# Receptor.net
KiCad netlist of a schematic drawn in Altium Designer
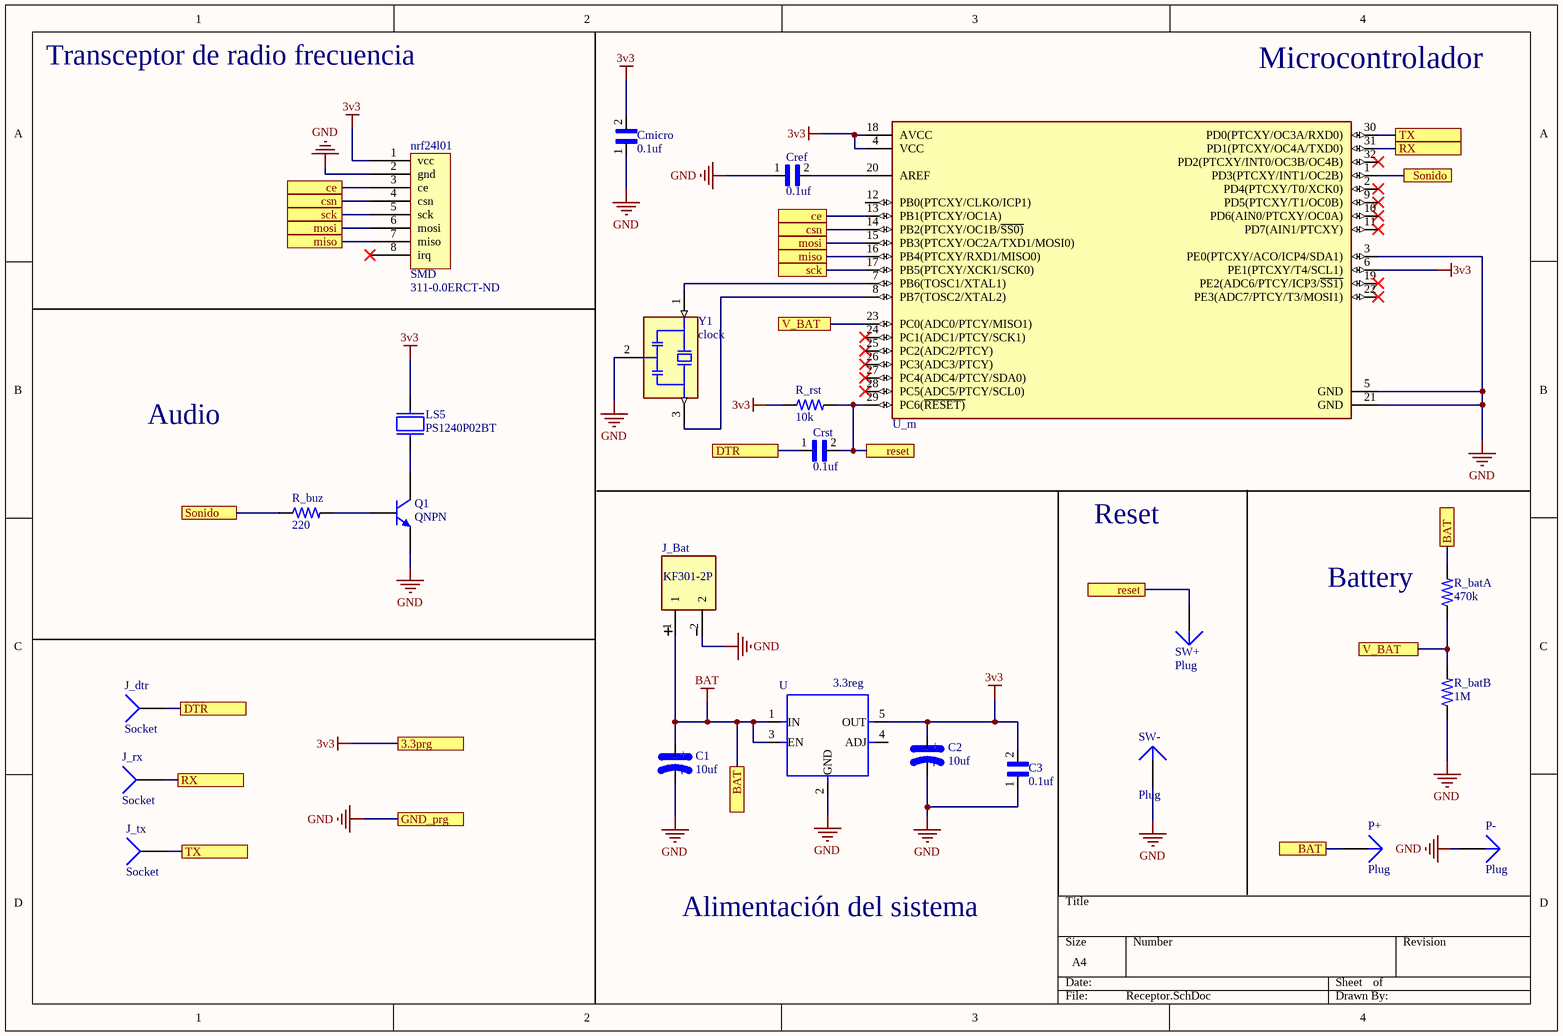
[diagram p0: Receptor.SchDoc]

(export (version "E")
  (design (tool "Eeschema 10.0.6"))
  (components
    (comp (ref "C1")
      (value "10uf")
      (footprint "CT1206")
      (description "10ÂµF Molded Tantalum Capacitors 20V 1206 _3216 Metric_ 5Ohm")
      (fields (field (name "MF") "KEMET") (field (name "MP") "T491A106M020AT"))
      (libsource (lib "1206_tantalio") (part "TANTALUM-SMD-10UF-20V-20%(1206)"))
    )
    (comp (ref "C2")
      (value "10uf")
      (footprint "CT1206")
      (description "10ÂµF Molded Tantalum Capacitors 20V 1206 _3216 Metric_ 5Ohm")
      (fields (field (name "MF") "KEMET") (field (name "MP") "T491A106M020AT"))
      (libsource (lib "1206_tantalio") (part "TANTALUM-SMD-10UF-20V-20%(1206)"))
    )
    (comp (ref "C3")
      (value "0.1uf")
      (footprint "CAPC2012X94N")
      (description "10000pF Â±5% 16V Ceramic Capacitor X7R 0805 _2012 Metric_")
      (fields (field (name "MF") "AVX") (field (name "MP") "0805YC103J4T2A"))
      (libsource (lib "") (part "0805YC103J4T2A_1"))
    )
    (comp (ref "Cmicro")
      (value "0.1uf")
      (footprint "CAPC2012X94N")
      (description "10000pF Â±5% 16V Ceramic Capacitor X7R 0805 _2012 Metric_")
      (fields (field (name "MF") "AVX") (field (name "MP") "0805YC103J4T2A"))
      (libsource (lib "") (part "0805YC103J4T2A_1"))
    )
    (comp (ref "Cref")
      (value "0.1uf")
      (footprint "CAPC2012X94N")
      (description "10000pF Â±5% 16V Ceramic Capacitor X7R 0805 _2012 Metric_")
      (fields (field (name "MF") "AVX") (field (name "MP") "0805YC103J4T2A"))
      (libsource (lib "v2CAP0805") (part "0805YC103J4T2A"))
    )
    (comp (ref "Crst")
      (value "0.1uf")
      (footprint "CAPC2012X94N")
      (description "10000pF Â±5% 16V Ceramic Capacitor X7R 0805 _2012 Metric_")
      (fields (field (name "MF") "AVX") (field (name "MP") "0805YC103J4T2A"))
      (libsource (lib "v2CAP0805") (part "0805YC103J4T2A"))
    )
    (comp (ref "J_Bat")
      (value "KF301-2P")
      (footprint "HANDSON_KF301-2P")
      (description "2 Pin Terminal Block 5mm Pitch")
      (fields (field (name "MF") "Handson Technology"))
      (libsource (lib "bornera") (part "KF301-2P"))
    )
    (comp (ref "J_dtr")
      (value "Socket")
      (footprint "PIN1")
      (fields (field (name "PUBLISHER") "Altium Limited"))
      (libsource (lib "Miscellaneous Connectors") (part "Socket"))
    )
    (comp (ref "J_rx")
      (value "Socket")
      (footprint "PIN1")
      (fields (field (name "PUBLISHER") "Altium Limited"))
      (libsource (lib "Miscellaneous Connectors") (part "Socket"))
    )
    (comp (ref "J_tx")
      (value "Socket")
      (footprint "PIN1")
      (fields (field (name "PUBLISHER") "Altium Limited"))
      (libsource (lib "Miscellaneous Connectors") (part "Socket"))
    )
    (comp (ref "LS5")
      (value "PS1240P02BT")
      (footprint "XDCR_PS1240P02BT")
      (description "Buzzers Transducer, Externally Driven Piezo 3V 4kHz 60dB @ 3V, 10cm Through Hole PC Pins")
      (fields (field (name "MF") "TDK"))
      (libsource (lib "buzzerGrande") (part "PS1240P02BT"))
    )
    (comp (ref "nrf24l01")
      (value "SMD")
      (footprint "NRF24L01")
      (fields (field (name "SUPPLIER PART NUMBER 1") "311-0.0ERCT-ND"))
      (libsource (lib "Schlib1") (part "nrf24l01_smd"))
    )
    (comp (ref "P+")
      (value "Plug")
      (footprint "PIN1")
      (fields (field (name "PUBLISHER") "Altium Limited"))
      (libsource (lib "Miscellaneous Connectors") (part "Plug"))
    )
    (comp (ref "P-")
      (value "Plug")
      (footprint "PIN1")
      (fields (field (name "PUBLISHER") "Altium Limited"))
      (libsource (lib "Miscellaneous Connectors") (part "Plug"))
    )
    (comp (ref "Q1")
      (value "QNPN")
      (footprint "SOT-23B_N")
      (description "NPN Bipolar Transistor")
      (fields (field (name "PUBLISHER") "Altium Limited"))
      (libsource (lib "Miscellaneous Devices") (part "QNPN"))
    )
    (comp (ref "R_batA")
      (value "470k")
      (footprint "RESC2012X65N")
      (description "RES 0.33 OHM 1% 1/4W 0805")
      (fields (field (name "MF") "TE Connectivity") (field (name "TOLERANCE") "1%"))
      (libsource (lib "RES0805") (part "2-2176053-0"))
    )
    (comp (ref "R_batB")
      (value "1M")
      (footprint "RESC2012X65N")
      (description "RES 0.33 OHM 1% 1/4W 0805")
      (fields (field (name "MF") "TE Connectivity") (field (name "TOLERANCE") "1%"))
      (libsource (lib "RES0805") (part "2-2176053-0"))
    )
    (comp (ref "R_buz")
      (value "220")
      (footprint "RESC2012X65N")
      (description "RES 0.33 OHM 1% 1/4W 0805")
      (fields (field (name "MF") "TE Connectivity") (field (name "TOLERANCE") "1%"))
      (libsource (lib "RES0805") (part "2-2176053-0"))
    )
    (comp (ref "R_rst")
      (value "10k")
      (footprint "RESC2012X65N")
      (description "RES 0.33 OHM 1% 1/4W 0805")
      (fields (field (name "MF") "TE Connectivity") (field (name "TOLERANCE") "1%"))
      (libsource (lib "RES0805") (part "2-2176053-0"))
    )
    (comp (ref "SW+")
      (value "Plug")
      (footprint "PIN1")
      (fields (field (name "PUBLISHER") "Altium Limited"))
      (libsource (lib "Miscellaneous Connectors") (part "Plug"))
    )
    (comp (ref "SW-")
      (value "Plug")
      (footprint "PIN1")
      (fields (field (name "PUBLISHER") "Altium Limited"))
      (libsource (lib "Miscellaneous Connectors") (part "Plug"))
    )
    (comp (ref "U")
      (value "3.3reg")
      (footprint "SOT-23-5")
      (description "Linear Voltage Regulator IC 1 Output 150mA SOT-23-5")
      (fields (field (name "MP") "MIC5205-3.3YM5-TR") (field (name "MF") "Microchip"))
      (libsource (lib "3.3mini") (part "PMIC-MIC5205-3.3YMSTR(SOT23-5)"))
    )
    (comp (ref "U_m")
      (value "ATMEGA328PB-AUR")
      (footprint "Microchip_C04-074_IPC_C")
      (libsource (lib "IC_Microchip_ATMEGA328PB-AUR_eec") (part "ATMEGA328PB-AUR"))
    )
    (comp (ref "Y1")
      (value "clock")
      (footprint "OSC_CSTCE8M00G52-R0")
      (description "8MHz Ceramic Resonator Built in Capacitor 10pF Â±0.2% -20Â°C ~ 80Â°C Surface Mount")
      (fields (field (name "MF") "Murata") (field (name "MP") "CSTCE8M00G52-R0"))
      (libsource (lib "CSTCE8M00G52-R0") (part "CSTCE8M00G52-R0"))
    )
  )
  (nets
    (net (code "1") (name "/DTR") (class "Default")
      (node (ref "Crst") (pin "1") (pinfunction "1_1") (pintype "passive"))
      (node (ref "J_dtr") (pin "1") (pinfunction "1_1") (pintype "passive"))
    )
    (net (code "2") (name "/RX") (class "Default")
      (node (ref "J_rx") (pin "1") (pinfunction "1_1") (pintype "passive"))
      (node (ref "U_m") (pin "31") (pinfunction "PD1(PTCXY/OC4A/TXD0)_31") (pintype "bidirectional"))
    )
    (net (code "3") (name "/Sonido") (class "Default")
      (node (ref "R_buz") (pin "1") (pinfunction "1_1") (pintype "passive"))
      (node (ref "U_m") (pin "1") (pinfunction "PD3(PTCXY/INT1/OC2B)_1") (pintype "bidirectional"))
    )
    (net (code "4") (name "/TX") (class "Default")
      (node (ref "J_tx") (pin "1") (pinfunction "1_1") (pintype "passive"))
      (node (ref "U_m") (pin "30") (pinfunction "PD0(PTCXY/OC3A/RXD0)_30") (pintype "bidirectional"))
    )
    (net (code "5") (name "/V_BAT") (class "Default")
      (node (ref "R_batA") (pin "1") (pinfunction "1_1") (pintype "passive"))
      (node (ref "R_batB") (pin "2") (pinfunction "2_2") (pintype "passive"))
      (node (ref "U_m") (pin "23") (pinfunction "PC0(ADC0/PTCY/MISO1)_23") (pintype "bidirectional"))
    )
    (net (code "6") (name "/ce") (class "Default")
      (node (ref "U_m") (pin "13") (pinfunction "PB1(PTCXY/OC1A)_13") (pintype "bidirectional"))
      (node (ref "nrf24l01") (pin "3") (pinfunction "ce_3") (pintype "passive"))
    )
    (net (code "7") (name "/csn") (class "Default")
      (node (ref "U_m") (pin "14") (pinfunction "PB2(PTCXY/OC1B/~{SS0)}_14") (pintype "bidirectional"))
      (node (ref "nrf24l01") (pin "4") (pinfunction "csn_4") (pintype "passive"))
    )
    (net (code "8") (name "/miso") (class "Default")
      (node (ref "U_m") (pin "16") (pinfunction "PB4(PTCXY/RXD1/MISO0)_16") (pintype "bidirectional"))
      (node (ref "nrf24l01") (pin "7") (pinfunction "miso_7") (pintype "passive"))
    )
    (net (code "9") (name "/mosi") (class "Default")
      (node (ref "U_m") (pin "15") (pinfunction "PB3(PTCXY/OC2A/TXD1/MOSI0)_15") (pintype "bidirectional"))
      (node (ref "nrf24l01") (pin "6") (pinfunction "mosi_6") (pintype "passive"))
    )
    (net (code "10") (name "/reset") (class "Default")
      (node (ref "Crst") (pin "2") (pinfunction "2_2") (pintype "passive"))
      (node (ref "R_rst") (pin "2") (pinfunction "2_2") (pintype "passive"))
      (node (ref "SW+") (pin "1") (pinfunction "1_1") (pintype "passive"))
      (node (ref "U_m") (pin "29") (pinfunction "PC6(~{RESET)}_29") (pintype "bidirectional"))
    )
    (net (code "11") (name "/sck") (class "Default")
      (node (ref "U_m") (pin "17") (pinfunction "PB5(PTCXY/XCK1/SCK0)_17") (pintype "bidirectional"))
      (node (ref "nrf24l01") (pin "5") (pinfunction "sck_5") (pintype "passive"))
    )
    (net (code "12") (name "3v3") (class "Default")
      (node (ref "C2") (pin "POS") (pinfunction "POS_POS") (pintype "passive"))
      (node (ref "C3") (pin "2") (pinfunction "2_2") (pintype "passive"))
      (node (ref "Cmicro") (pin "2") (pinfunction "2_2") (pintype "passive"))
      (node (ref "LS5") (pin "1") (pinfunction "1_1") (pintype "passive"))
      (node (ref "R_rst") (pin "1") (pinfunction "1_1") (pintype "passive"))
      (node (ref "U") (pin "5") (pinfunction "OUT_5") (pintype "bidirectional"))
      (node (ref "U_m") (pin "18") (pinfunction "AVCC_18") (pintype "power_in"))
      (node (ref "U_m") (pin "4") (pinfunction "VCC_4") (pintype "power_in"))
      (node (ref "U_m") (pin "6") (pinfunction "PE1(PTCXY/T4/SCL1)_6") (pintype "bidirectional"))
      (node (ref "nrf24l01") (pin "1") (pinfunction "vcc_1") (pintype "passive"))
    )
    (net (code "13") (name "BAT") (class "Default")
      (node (ref "C1") (pin "POS") (pinfunction "POS_POS") (pintype "passive"))
      (node (ref "J_Bat") (pin "1") (pinfunction "1_1") (pintype "passive"))
      (node (ref "P+") (pin "1") (pinfunction "1_1") (pintype "passive"))
      (node (ref "R_batA") (pin "2") (pinfunction "2_2") (pintype "passive"))
      (node (ref "U") (pin "1") (pinfunction "IN_1") (pintype "bidirectional"))
      (node (ref "U") (pin "3") (pinfunction "EN_3") (pintype "bidirectional"))
    )
    (net (code "14") (name "GND") (class "Default")
      (node (ref "C1") (pin "NEG") (pinfunction "NEG_NEG") (pintype "passive"))
      (node (ref "C2") (pin "NEG") (pinfunction "NEG_NEG") (pintype "passive"))
      (node (ref "C3") (pin "1") (pinfunction "1_1") (pintype "passive"))
      (node (ref "Cmicro") (pin "1") (pinfunction "1_1") (pintype "passive"))
      (node (ref "Cref") (pin "1") (pinfunction "1_1") (pintype "passive"))
      (node (ref "J_Bat") (pin "2") (pinfunction "2_2") (pintype "passive"))
      (node (ref "P-") (pin "1") (pinfunction "1_1") (pintype "passive"))
      (node (ref "Q1") (pin "3") (pinfunction "E_3") (pintype "passive"))
      (node (ref "R_batB") (pin "1") (pinfunction "1_1") (pintype "passive"))
      (node (ref "SW-") (pin "1") (pinfunction "1_1") (pintype "passive"))
      (node (ref "U") (pin "2") (pinfunction "GND_2") (pintype "bidirectional"))
      (node (ref "U_m") (pin "21") (pinfunction "GND_21") (pintype "power_in"))
      (node (ref "U_m") (pin "3") (pinfunction "PE0(PTCXY/ACO/ICP4/SDA1)_3") (pintype "bidirectional"))
      (node (ref "U_m") (pin "5") (pinfunction "GND_5") (pintype "power_in"))
      (node (ref "Y1") (pin "2") (pinfunction "GND_2") (pintype "power_in"))
      (node (ref "nrf24l01") (pin "2") (pinfunction "gnd_2") (pintype "passive"))
    )
    (net (code "15") (name "Net-(Q1-B)") (class "Default")
      (node (ref "Q1") (pin "2") (pinfunction "B_2") (pintype "passive"))
      (node (ref "R_buz") (pin "2") (pinfunction "2_2") (pintype "passive"))
    )
    (net (code "16") (name "Net-(Q1-C)") (class "Default")
      (node (ref "LS5") (pin "2") (pinfunction "2_2") (pintype "passive"))
      (node (ref "Q1") (pin "1") (pinfunction "C_1") (pintype "passive"))
    )
    (net (code "17") (name "Net-(U_m-AREF)") (class "Default")
      (node (ref "Cref") (pin "2") (pinfunction "2_2") (pintype "passive"))
      (node (ref "U_m") (pin "20") (pinfunction "AREF_20") (pintype "power_in"))
    )
    (net (code "18") (name "Net-(U_m-PB6(TOSC1{slash}XTAL1))") (class "Default")
      (node (ref "U_m") (pin "7") (pinfunction "PB6(TOSC1/XTAL1)_7") (pintype "bidirectional"))
      (node (ref "Y1") (pin "1") (pinfunction "IN_1") (pintype "input"))
    )
    (net (code "19") (name "Net-(U_m-PB7(TOSC2{slash}XTAL2))") (class "Default")
      (node (ref "U_m") (pin "8") (pinfunction "PB7(TOSC2/XTAL2)_8") (pintype "bidirectional"))
      (node (ref "Y1") (pin "3") (pinfunction "OUT_3") (pintype "output"))
    )
    (net (code "20") (name "unconnected-(U-ADJ-Pad4)") (class "Default")
      (node (ref "U") (pin "4") (pinfunction "ADJ_4") (pintype "bidirectional"))
    )
    (net (code "21") (name "unconnected-(U_m-PB0(PTCXY{slash}CLKO{slash}ICP1)-Pad12)") (class "Default")
      (node (ref "U_m") (pin "12") (pinfunction "PB0(PTCXY/CLKO/ICP1)_12") (pintype "bidirectional"))
    )
    (net (code "22") (name "unconnected-(U_m-PC1(ADC1{slash}PTCY{slash}SCK1)-Pad24)") (class "Default")
      (node (ref "U_m") (pin "24") (pinfunction "PC1(ADC1/PTCY/SCK1)_24") (pintype "bidirectional+no_connect"))
    )
    (net (code "23") (name "unconnected-(U_m-PC2(ADC2{slash}PTCY)-Pad25)") (class "Default")
      (node (ref "U_m") (pin "25") (pinfunction "PC2(ADC2/PTCY)_25") (pintype "bidirectional+no_connect"))
    )
    (net (code "24") (name "unconnected-(U_m-PC3(ADC3{slash}PTCY)-Pad26)") (class "Default")
      (node (ref "U_m") (pin "26") (pinfunction "PC3(ADC3/PTCY)_26") (pintype "bidirectional+no_connect"))
    )
    (net (code "25") (name "unconnected-(U_m-PC4(ADC4{slash}PTCY{slash}SDA0)-Pad27)") (class "Default")
      (node (ref "U_m") (pin "27") (pinfunction "PC4(ADC4/PTCY/SDA0)_27") (pintype "bidirectional+no_connect"))
    )
    (net (code "26") (name "unconnected-(U_m-PC5(ADC5{slash}PTCY{slash}SCL0)-Pad28)") (class "Default")
      (node (ref "U_m") (pin "28") (pinfunction "PC5(ADC5/PTCY/SCL0)_28") (pintype "bidirectional+no_connect"))
    )
    (net (code "27") (name "unconnected-(U_m-PD2(PTCXY{slash}INT0{slash}OC3B{slash}OC4B)-Pad32)") (class "Default")
      (node (ref "U_m") (pin "32") (pinfunction "PD2(PTCXY/INT0/OC3B/OC4B)_32") (pintype "bidirectional+no_connect"))
    )
    (net (code "28") (name "unconnected-(U_m-PD4(PTCXY{slash}T0{slash}XCK0)-Pad2)") (class "Default")
      (node (ref "U_m") (pin "2") (pinfunction "PD4(PTCXY/T0/XCK0)_2") (pintype "bidirectional+no_connect"))
    )
    (net (code "29") (name "unconnected-(U_m-PD5(PTCXY{slash}T1{slash}OC0B)-Pad9)") (class "Default")
      (node (ref "U_m") (pin "9") (pinfunction "PD5(PTCXY/T1/OC0B)_9") (pintype "bidirectional+no_connect"))
    )
    (net (code "30") (name "unconnected-(U_m-PD6(AIN0{slash}PTCXY{slash}OC0A)-Pad10)") (class "Default")
      (node (ref "U_m") (pin "10") (pinfunction "PD6(AIN0/PTCXY/OC0A)_10") (pintype "bidirectional+no_connect"))
    )
    (net (code "31") (name "unconnected-(U_m-PD7(AIN1{slash}PTCXY)-Pad11)") (class "Default")
      (node (ref "U_m") (pin "11") (pinfunction "PD7(AIN1/PTCXY)_11") (pintype "bidirectional+no_connect"))
    )
    (net (code "32") (name "unconnected-(U_m-PE2(ADC6{slash}PTCY{slash}ICP3{slash}~{SS1)}-Pad19)") (class "Default")
      (node (ref "U_m") (pin "19") (pinfunction "PE2(ADC6/PTCY/ICP3/~{SS1)}_19") (pintype "bidirectional+no_connect"))
    )
    (net (code "33") (name "unconnected-(U_m-PE3(ADC7{slash}PTCY{slash}T3{slash}MOSI1)-Pad22)") (class "Default")
      (node (ref "U_m") (pin "22") (pinfunction "PE3(ADC7/PTCY/T3/MOSI1)_22") (pintype "bidirectional+no_connect"))
    )
    (net (code "34") (name "unconnected-(nrf24l01-irq-Pad8)") (class "Default")
      (node (ref "nrf24l01") (pin "8") (pinfunction "irq_8") (pintype "passive+no_connect"))
    )
  )
)
